# ContactlessMain.net
KiCad netlist of a schematic drawn in EAGLE
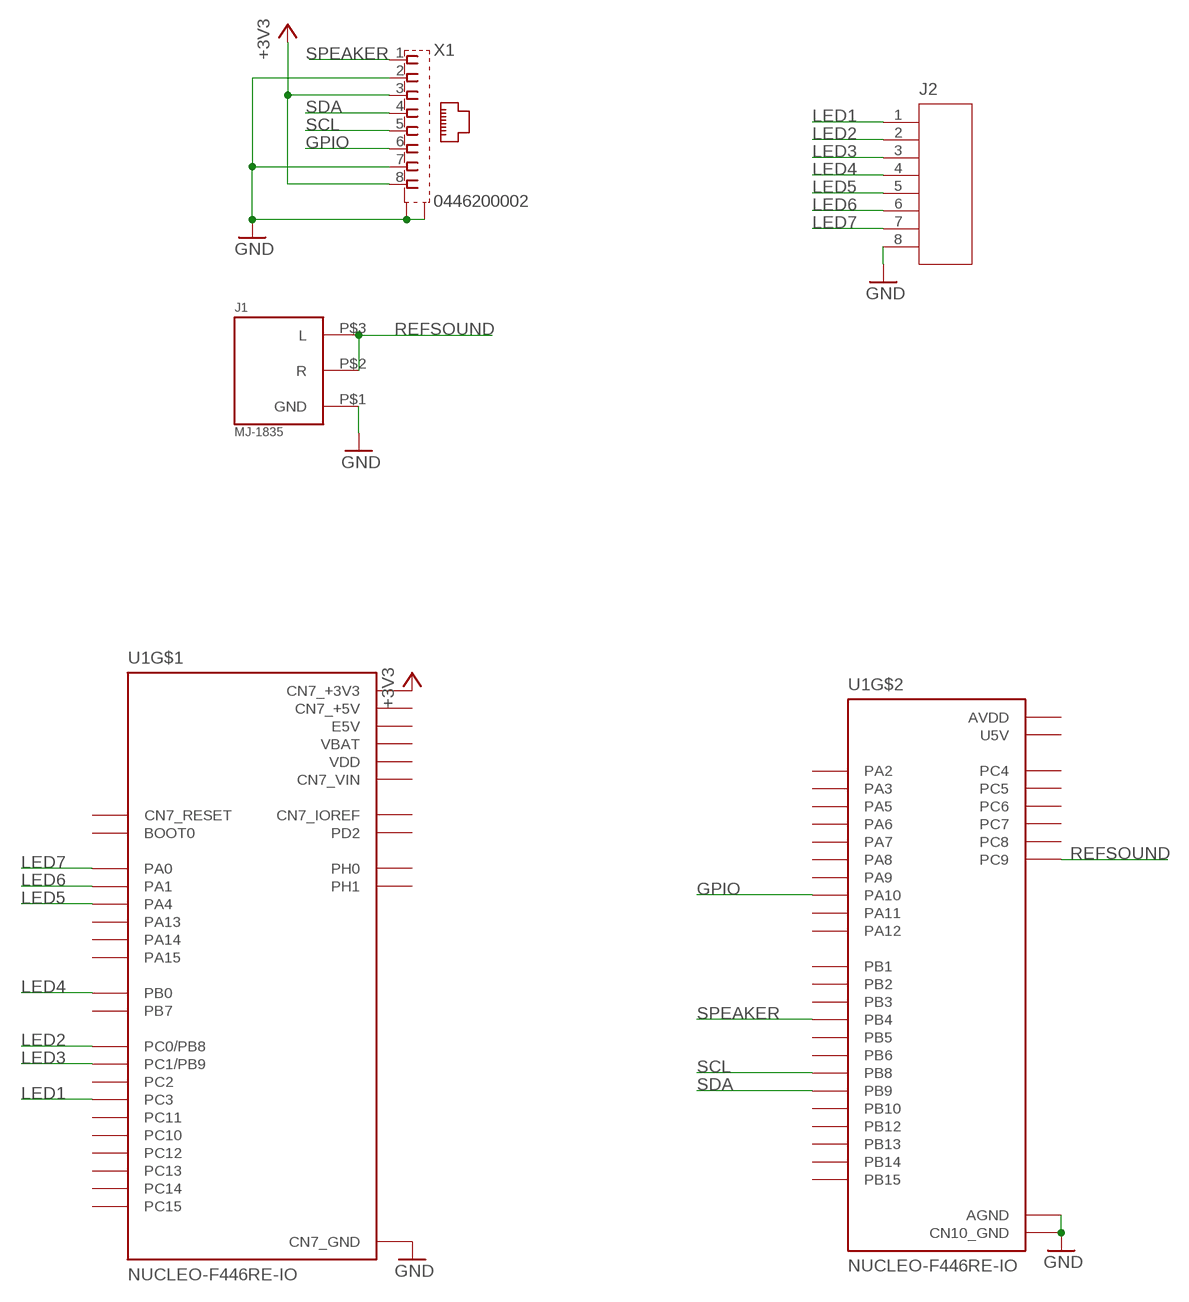
[diagram p0: schematic, sheet 1]

(export (version "E")
  (design (tool "Eeschema 10.0.6"))
  (components
    (comp (ref "J1")
      (value "MJ-1835")
      (footprint "eagle-import:MJ-1835")
      (libsource (lib "eagle-import") (part "MJ-1835"))
    )
    (comp (ref "J2")
      (value "PINHEADER-818*1")
      (footprint "eagle-import:PINHEADER-8_1")
      (libsource (lib "eagle-import") (part "PINHEADER-8181"))
    )
    (comp (ref "U1")
      (value "NUCLEO-F446RE-IO")
      (footprint "eagle-import:MODULE_NUCLEO-F446RE")
      (libsource (lib "eagle-import") (part "NUCLEO-F446RE-IO"))
    )
    (comp (ref "X1")
      (value "0446200002")
      (footprint "eagle-import:0446200002")
      (fields (field (name "MF") "MOLEX"))
      (libsource (lib "eagle-import") (part "0446200002"))
    )
  )
  (nets
    (net (code "1") (name "+3V3") (class "Default")
      (node (ref "U1") (pin "CN7_16") (pinfunction "CN7_+3V3_CN7_16") (pintype "power_in"))
      (node (ref "X1") (pin "3") (pinfunction "3_3") (pintype "passive"))
      (node (ref "X1") (pin "8") (pinfunction "8_8") (pintype "passive"))
    )
    (net (code "2") (name "/AVDD") (class "Default")
      (node (ref "U1") (pin "CN10_7") (pinfunction "AVDD_CN10_7") (pintype "power_in"))
    )
    (net (code "3") (name "/CN7_+5V") (class "Default")
      (node (ref "U1") (pin "CN7_18") (pinfunction "CN7_+5V_CN7_18") (pintype "power_in"))
    )
    (net (code "4") (name "/CN7_VIN") (class "Default")
      (node (ref "U1") (pin "CN7_24") (pinfunction "CN7_VIN_CN7_24") (pintype "power_in"))
    )
    (net (code "5") (name "/E5V") (class "Default")
      (node (ref "U1") (pin "CN7_6") (pinfunction "E5V_CN7_6") (pintype "power_in"))
    )
    (net (code "6") (name "/GPIO") (class "Default")
      (node (ref "U1") (pin "CN10_33") (pinfunction "PA10_CN10_33") (pintype "bidirectional"))
      (node (ref "X1") (pin "6") (pinfunction "6_6") (pintype "passive"))
    )
    (net (code "7") (name "/LED1") (class "Default")
      (node (ref "J2") (pin "1") (pinfunction "1_1") (pintype "bidirectional"))
      (node (ref "U1") (pin "CN7_37") (pinfunction "PC3_CN7_37") (pintype "bidirectional"))
    )
    (net (code "8") (name "/LED2") (class "Default")
      (node (ref "J2") (pin "2") (pinfunction "2_2") (pintype "bidirectional"))
      (node (ref "U1") (pin "CN7_38") (pinfunction "PC0/PB8_CN7_38") (pintype "bidirectional"))
    )
    (net (code "9") (name "/LED3") (class "Default")
      (node (ref "J2") (pin "3") (pinfunction "3_3") (pintype "bidirectional"))
      (node (ref "U1") (pin "CN7_36") (pinfunction "PC1/PB9_CN7_36") (pintype "bidirectional"))
    )
    (net (code "10") (name "/LED4") (class "Default")
      (node (ref "J2") (pin "4") (pinfunction "4_4") (pintype "bidirectional"))
      (node (ref "U1") (pin "CN7_34") (pinfunction "PB0_CN7_34") (pintype "bidirectional"))
    )
    (net (code "11") (name "/LED5") (class "Default")
      (node (ref "J2") (pin "5") (pinfunction "5_5") (pintype "bidirectional"))
      (node (ref "U1") (pin "CN7_32") (pinfunction "PA4_CN7_32") (pintype "bidirectional"))
    )
    (net (code "12") (name "/LED6") (class "Default")
      (node (ref "J2") (pin "6") (pinfunction "6_6") (pintype "bidirectional"))
      (node (ref "U1") (pin "CN7_30") (pinfunction "PA1_CN7_30") (pintype "bidirectional"))
    )
    (net (code "13") (name "/LED7") (class "Default")
      (node (ref "J2") (pin "7") (pinfunction "7_7") (pintype "bidirectional"))
      (node (ref "U1") (pin "CN7_28") (pinfunction "PA0_CN7_28") (pintype "bidirectional"))
    )
    (net (code "14") (name "/REFSOUND") (class "Default")
      (node (ref "J1") (pin "P$2") (pinfunction "R_P$2") (pintype "bidirectional"))
      (node (ref "J1") (pin "P$3") (pinfunction "L_P$3") (pintype "bidirectional"))
      (node (ref "U1") (pin "CN10_1") (pinfunction "PC9_CN10_1") (pintype "bidirectional"))
    )
    (net (code "15") (name "/SCL") (class "Default")
      (node (ref "U1") (pin "CN10_3") (pinfunction "PB8_CN10_3") (pintype "bidirectional"))
      (node (ref "X1") (pin "5") (pinfunction "5_5") (pintype "passive"))
    )
    (net (code "16") (name "/SDA") (class "Default")
      (node (ref "U1") (pin "CN10_5") (pinfunction "PB9_CN10_5") (pintype "bidirectional"))
      (node (ref "X1") (pin "4") (pinfunction "4_4") (pintype "passive"))
    )
    (net (code "17") (name "/SPEAKER") (class "Default")
      (node (ref "U1") (pin "CN10_27") (pinfunction "PB4_CN10_27") (pintype "bidirectional"))
      (node (ref "X1") (pin "1") (pinfunction "1_1") (pintype "passive"))
    )
    (net (code "18") (name "/U5V") (class "Default")
      (node (ref "U1") (pin "CN10_8") (pinfunction "U5V_CN10_8") (pintype "power_in"))
    )
    (net (code "19") (name "/VBAT") (class "Default")
      (node (ref "U1") (pin "CN7_33") (pinfunction "VBAT_CN7_33") (pintype "power_in"))
    )
    (net (code "20") (name "/VDD") (class "Default")
      (node (ref "U1") (pin "CN7_5") (pinfunction "VDD_CN7_5") (pintype "power_in"))
    )
    (net (code "21") (name "GND") (class "Default")
      (node (ref "J1") (pin "P$1") (pinfunction "GND_P$1") (pintype "bidirectional"))
      (node (ref "J2") (pin "8") (pinfunction "8_8") (pintype "bidirectional"))
      (node (ref "U1") (pin "CN10_20") (pinfunction "CN10_GND_CN10_20") (pintype "power_in"))
      (node (ref "U1") (pin "CN10_32") (pinfunction "AGND_CN10_32") (pintype "power_in"))
      (node (ref "U1") (pin "CN10_9") (pinfunction "CN10_GND_CN10_9") (pintype "power_in"))
      (node (ref "U1") (pin "CN7_19") (pinfunction "CN7_GND_CN7_19") (pintype "power_in"))
      (node (ref "U1") (pin "CN7_20") (pinfunction "CN7_GND_CN7_20") (pintype "power_in"))
      (node (ref "U1") (pin "CN7_22") (pinfunction "CN7_GND_CN7_22") (pintype "power_in"))
      (node (ref "U1") (pin "CN7_8") (pinfunction "CN7_GND_CN7_8") (pintype "power_in"))
      (node (ref "X1") (pin "2") (pinfunction "2_2") (pintype "passive"))
      (node (ref "X1") (pin "7") (pinfunction "7_7") (pintype "passive"))
      (node (ref "X1") (pin "S@1") (pinfunction "S1_S@1") (pintype "passive"))
      (node (ref "X1") (pin "S@2") (pinfunction "S2_S@2") (pintype "passive"))
    )
    (net (code "22") (name "unconnected-(U1A-BOOT0-PadCN7_7)") (class "Default")
      (node (ref "U1") (pin "CN7_7") (pinfunction "BOOT0_CN7_7") (pintype "bidirectional"))
    )
    (net (code "23") (name "unconnected-(U1A-CN7_IOREF-PadCN7_12)") (class "Default")
      (node (ref "U1") (pin "CN7_12") (pinfunction "CN7_IOREF_CN7_12") (pintype "bidirectional"))
    )
    (net (code "24") (name "unconnected-(U1A-CN7_RESET-PadCN7_14)") (class "Default")
      (node (ref "U1") (pin "CN7_14") (pinfunction "CN7_RESET_CN7_14") (pintype "bidirectional"))
    )
    (net (code "25") (name "unconnected-(U1A-PA13-PadCN7_13)") (class "Default")
      (node (ref "U1") (pin "CN7_13") (pinfunction "PA13_CN7_13") (pintype "bidirectional"))
    )
    (net (code "26") (name "unconnected-(U1A-PA14-PadCN7_15)") (class "Default")
      (node (ref "U1") (pin "CN7_15") (pinfunction "PA14_CN7_15") (pintype "bidirectional"))
    )
    (net (code "27") (name "unconnected-(U1A-PA15-PadCN7_17)") (class "Default")
      (node (ref "U1") (pin "CN7_17") (pinfunction "PA15_CN7_17") (pintype "bidirectional"))
    )
    (net (code "28") (name "unconnected-(U1A-PB7-PadCN7_21)") (class "Default")
      (node (ref "U1") (pin "CN7_21") (pinfunction "PB7_CN7_21") (pintype "bidirectional"))
    )
    (net (code "29") (name "unconnected-(U1A-PC2-PadCN7_35)") (class "Default")
      (node (ref "U1") (pin "CN7_35") (pinfunction "PC2_CN7_35") (pintype "bidirectional"))
    )
    (net (code "30") (name "unconnected-(U1A-PC10-PadCN7_1)") (class "Default")
      (node (ref "U1") (pin "CN7_1") (pinfunction "PC10_CN7_1") (pintype "bidirectional"))
    )
    (net (code "31") (name "unconnected-(U1A-PC11-PadCN7_2)") (class "Default")
      (node (ref "U1") (pin "CN7_2") (pinfunction "PC11_CN7_2") (pintype "bidirectional"))
    )
    (net (code "32") (name "unconnected-(U1A-PC12-PadCN7_3)") (class "Default")
      (node (ref "U1") (pin "CN7_3") (pinfunction "PC12_CN7_3") (pintype "bidirectional"))
    )
    (net (code "33") (name "unconnected-(U1A-PC13-PadCN7_23)") (class "Default")
      (node (ref "U1") (pin "CN7_23") (pinfunction "PC13_CN7_23") (pintype "bidirectional"))
    )
    (net (code "34") (name "unconnected-(U1A-PC14-PadCN7_25)") (class "Default")
      (node (ref "U1") (pin "CN7_25") (pinfunction "PC14_CN7_25") (pintype "bidirectional"))
    )
    (net (code "35") (name "unconnected-(U1A-PC15-PadCN7_27)") (class "Default")
      (node (ref "U1") (pin "CN7_27") (pinfunction "PC15_CN7_27") (pintype "bidirectional"))
    )
    (net (code "36") (name "unconnected-(U1A-PD2-PadCN7_4)") (class "Default")
      (node (ref "U1") (pin "CN7_4") (pinfunction "PD2_CN7_4") (pintype "bidirectional"))
    )
    (net (code "37") (name "unconnected-(U1A-PH0-PadCN7_29)") (class "Default")
      (node (ref "U1") (pin "CN7_29") (pinfunction "PH0_CN7_29") (pintype "bidirectional"))
    )
    (net (code "38") (name "unconnected-(U1A-PH1-PadCN7_31)") (class "Default")
      (node (ref "U1") (pin "CN7_31") (pinfunction "PH1_CN7_31") (pintype "bidirectional"))
    )
    (net (code "39") (name "unconnected-(U1B-PA2-PadCN10_35)") (class "Default")
      (node (ref "U1") (pin "CN10_35") (pinfunction "PA2_CN10_35") (pintype "bidirectional"))
    )
    (net (code "40") (name "unconnected-(U1B-PA3-PadCN10_37)") (class "Default")
      (node (ref "U1") (pin "CN10_37") (pinfunction "PA3_CN10_37") (pintype "bidirectional"))
    )
    (net (code "41") (name "unconnected-(U1B-PA5-PadCN10_11)") (class "Default")
      (node (ref "U1") (pin "CN10_11") (pinfunction "PA5_CN10_11") (pintype "bidirectional"))
    )
    (net (code "42") (name "unconnected-(U1B-PA6-PadCN10_13)") (class "Default")
      (node (ref "U1") (pin "CN10_13") (pinfunction "PA6_CN10_13") (pintype "bidirectional"))
    )
    (net (code "43") (name "unconnected-(U1B-PA7-PadCN10_15)") (class "Default")
      (node (ref "U1") (pin "CN10_15") (pinfunction "PA7_CN10_15") (pintype "bidirectional"))
    )
    (net (code "44") (name "unconnected-(U1B-PA8-PadCN10_23)") (class "Default")
      (node (ref "U1") (pin "CN10_23") (pinfunction "PA8_CN10_23") (pintype "bidirectional"))
    )
    (net (code "45") (name "unconnected-(U1B-PA9-PadCN10_21)") (class "Default")
      (node (ref "U1") (pin "CN10_21") (pinfunction "PA9_CN10_21") (pintype "bidirectional"))
    )
    (net (code "46") (name "unconnected-(U1B-PA11-PadCN10_14)") (class "Default")
      (node (ref "U1") (pin "CN10_14") (pinfunction "PA11_CN10_14") (pintype "bidirectional"))
    )
    (net (code "47") (name "unconnected-(U1B-PA12-PadCN10_12)") (class "Default")
      (node (ref "U1") (pin "CN10_12") (pinfunction "PA12_CN10_12") (pintype "bidirectional"))
    )
    (net (code "48") (name "unconnected-(U1B-PB1-PadCN10_24)") (class "Default")
      (node (ref "U1") (pin "CN10_24") (pinfunction "PB1_CN10_24") (pintype "bidirectional"))
    )
    (net (code "49") (name "unconnected-(U1B-PB2-PadCN10_22)") (class "Default")
      (node (ref "U1") (pin "CN10_22") (pinfunction "PB2_CN10_22") (pintype "bidirectional"))
    )
    (net (code "50") (name "unconnected-(U1B-PB3-PadCN10_31)") (class "Default")
      (node (ref "U1") (pin "CN10_31") (pinfunction "PB3_CN10_31") (pintype "bidirectional"))
    )
    (net (code "51") (name "unconnected-(U1B-PB5-PadCN10_29)") (class "Default")
      (node (ref "U1") (pin "CN10_29") (pinfunction "PB5_CN10_29") (pintype "bidirectional"))
    )
    (net (code "52") (name "unconnected-(U1B-PB6-PadCN10_17)") (class "Default")
      (node (ref "U1") (pin "CN10_17") (pinfunction "PB6_CN10_17") (pintype "bidirectional"))
    )
    (net (code "53") (name "unconnected-(U1B-PB10-PadCN10_25)") (class "Default")
      (node (ref "U1") (pin "CN10_25") (pinfunction "PB10_CN10_25") (pintype "bidirectional"))
    )
    (net (code "54") (name "unconnected-(U1B-PB12-PadCN10_16)") (class "Default")
      (node (ref "U1") (pin "CN10_16") (pinfunction "PB12_CN10_16") (pintype "bidirectional"))
    )
    (net (code "55") (name "unconnected-(U1B-PB13-PadCN10_30)") (class "Default")
      (node (ref "U1") (pin "CN10_30") (pinfunction "PB13_CN10_30") (pintype "bidirectional"))
    )
    (net (code "56") (name "unconnected-(U1B-PB14-PadCN10_28)") (class "Default")
      (node (ref "U1") (pin "CN10_28") (pinfunction "PB14_CN10_28") (pintype "bidirectional"))
    )
    (net (code "57") (name "unconnected-(U1B-PB15-PadCN10_26)") (class "Default")
      (node (ref "U1") (pin "CN10_26") (pinfunction "PB15_CN10_26") (pintype "bidirectional"))
    )
    (net (code "58") (name "unconnected-(U1B-PC4-PadCN10_34)") (class "Default")
      (node (ref "U1") (pin "CN10_34") (pinfunction "PC4_CN10_34") (pintype "bidirectional"))
    )
    (net (code "59") (name "unconnected-(U1B-PC5-PadCN10_6)") (class "Default")
      (node (ref "U1") (pin "CN10_6") (pinfunction "PC5_CN10_6") (pintype "bidirectional"))
    )
    (net (code "60") (name "unconnected-(U1B-PC6-PadCN10_4)") (class "Default")
      (node (ref "U1") (pin "CN10_4") (pinfunction "PC6_CN10_4") (pintype "bidirectional"))
    )
    (net (code "61") (name "unconnected-(U1B-PC7-PadCN10_19)") (class "Default")
      (node (ref "U1") (pin "CN10_19") (pinfunction "PC7_CN10_19") (pintype "bidirectional"))
    )
    (net (code "62") (name "unconnected-(U1B-PC8-PadCN10_2)") (class "Default")
      (node (ref "U1") (pin "CN10_2") (pinfunction "PC8_CN10_2") (pintype "bidirectional"))
    )
  )
)
